# big_seven_v0_1.net
KiCad netlist of a schematic drawn in EAGLE
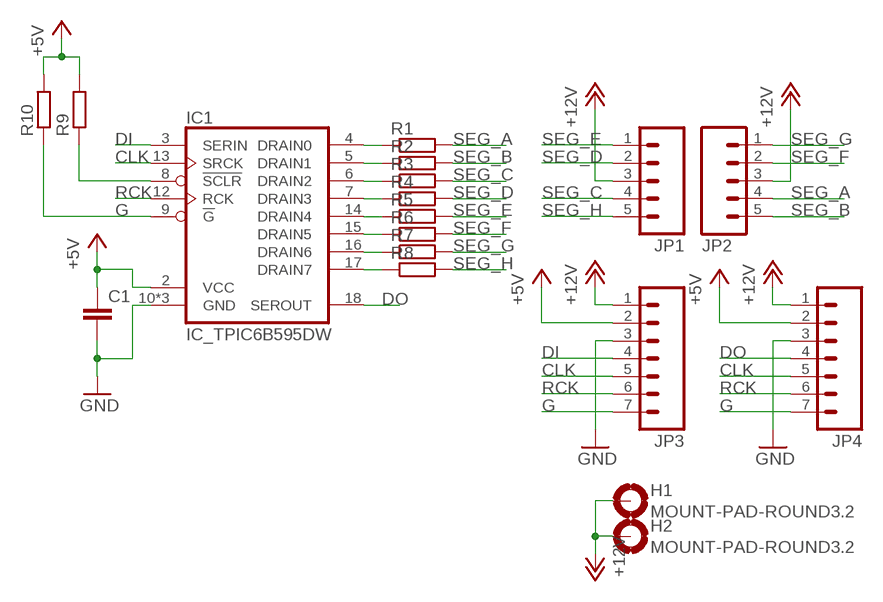
[diagram p0: schematic, sheet 1]

(export (version "E")
  (design (tool "Eeschema 10.0.6"))
  (components
    (comp (ref "C1")
      (value "C-EUC0805")
      (footprint "eagle-import:C0805")
      (libsource (lib "eagle-import") (part "C-EUC0805"))
    )
    (comp (ref "H1")
      (value "MOUNT-PAD-ROUND3.2")
      (footprint "eagle-import:3,2-PAD")
      (libsource (lib "eagle-import") (part "MOUNT-PAD-ROUND3.2"))
    )
    (comp (ref "H2")
      (value "MOUNT-PAD-ROUND3.2")
      (footprint "eagle-import:3,2-PAD")
      (libsource (lib "eagle-import") (part "MOUNT-PAD-ROUND3.2"))
    )
    (comp (ref "IC1")
      (value "IC_TPIC6B595DW")
      (footprint "eagle-import:SOIC-20")
      (libsource (lib "eagle-import") (part "IC_TPIC6B595DW"))
    )
    (comp (ref "JP1")
      (value "M05PTH")
      (footprint "eagle-import:1X05")
      (libsource (lib "eagle-import") (part "M05PTH"))
    )
    (comp (ref "JP2")
      (value "M05PTH")
      (footprint "eagle-import:1X05")
      (libsource (lib "eagle-import") (part "M05PTH"))
    )
    (comp (ref "JP3")
      (value "M07LONGPADS")
      (footprint "eagle-import:1X07_LONGPADS")
      (libsource (lib "eagle-import") (part "M07LONGPADS"))
    )
    (comp (ref "JP4")
      (value "M07LONGPADS")
      (footprint "eagle-import:1X07_LONGPADS")
      (libsource (lib "eagle-import") (part "M07LONGPADS"))
    )
    (comp (ref "R1")
      (value "R-EU_M0805")
      (footprint "eagle-import:M0805")
      (libsource (lib "eagle-import") (part "R-EU_M0805"))
    )
    (comp (ref "R2")
      (value "R-EU_M0805")
      (footprint "eagle-import:M0805")
      (libsource (lib "eagle-import") (part "R-EU_M0805"))
    )
    (comp (ref "R3")
      (value "R-EU_M0805")
      (footprint "eagle-import:M0805")
      (libsource (lib "eagle-import") (part "R-EU_M0805"))
    )
    (comp (ref "R4")
      (value "R-EU_M0805")
      (footprint "eagle-import:M0805")
      (libsource (lib "eagle-import") (part "R-EU_M0805"))
    )
    (comp (ref "R5")
      (value "R-EU_M0805")
      (footprint "eagle-import:M0805")
      (libsource (lib "eagle-import") (part "R-EU_M0805"))
    )
    (comp (ref "R6")
      (value "R-EU_M0805")
      (footprint "eagle-import:M0805")
      (libsource (lib "eagle-import") (part "R-EU_M0805"))
    )
    (comp (ref "R7")
      (value "R-EU_M0805")
      (footprint "eagle-import:M0805")
      (libsource (lib "eagle-import") (part "R-EU_M0805"))
    )
    (comp (ref "R8")
      (value "R-EU_M0805")
      (footprint "eagle-import:M0805")
      (libsource (lib "eagle-import") (part "R-EU_M0805"))
    )
    (comp (ref "R9")
      (value "R-EU_M0805")
      (footprint "eagle-import:M0805")
      (libsource (lib "eagle-import") (part "R-EU_M0805"))
    )
    (comp (ref "R10")
      (value "R-EU_M0805")
      (footprint "eagle-import:M0805")
      (libsource (lib "eagle-import") (part "R-EU_M0805"))
    )
  )
  (nets
    (net (code "1") (name "+5V") (class "Default")
      (node (ref "C1") (pin "1") (pinfunction "1_1") (pintype "passive"))
      (node (ref "IC1") (pin "2") (pinfunction "VCC_2") (pintype "power_in"))
      (node (ref "JP3") (pin "2") (pinfunction "2_2") (pintype "passive"))
      (node (ref "JP4") (pin "2") (pinfunction "2_2") (pintype "passive"))
      (node (ref "R10") (pin "2") (pinfunction "2_2") (pintype "passive"))
      (node (ref "R9") (pin "2") (pinfunction "2_2") (pintype "passive"))
    )
    (net (code "2") (name "+12V") (class "Default")
      (node (ref "H1") (pin "B3,2") (pinfunction "MOUNT_B3,2") (pintype "passive"))
      (node (ref "H2") (pin "B3,2") (pinfunction "MOUNT_B3,2") (pintype "passive"))
      (node (ref "JP1") (pin "3") (pinfunction "3_3") (pintype "passive"))
      (node (ref "JP2") (pin "3") (pinfunction "3_3") (pintype "passive"))
      (node (ref "JP3") (pin "1") (pinfunction "1_1") (pintype "passive"))
      (node (ref "JP4") (pin "1") (pinfunction "1_1") (pintype "passive"))
    )
    (net (code "3") (name "/CLK") (class "Default")
      (node (ref "IC1") (pin "13") (pinfunction "SRCK_13") (pintype "input"))
      (node (ref "JP3") (pin "5") (pinfunction "5_5") (pintype "passive"))
      (node (ref "JP4") (pin "5") (pinfunction "5_5") (pintype "passive"))
    )
    (net (code "4") (name "/DI") (class "Default")
      (node (ref "IC1") (pin "3") (pinfunction "SERIN_3") (pintype "input"))
      (node (ref "JP3") (pin "4") (pinfunction "4_4") (pintype "passive"))
    )
    (net (code "5") (name "/DO") (class "Default")
      (node (ref "IC1") (pin "18") (pinfunction "SEROUT_18") (pintype "output"))
      (node (ref "JP4") (pin "4") (pinfunction "4_4") (pintype "passive"))
    )
    (net (code "6") (name "/G") (class "Default")
      (node (ref "IC1") (pin "9") (pinfunction "~{G}_9") (pintype "input"))
      (node (ref "JP3") (pin "7") (pinfunction "7_7") (pintype "passive"))
      (node (ref "JP4") (pin "7") (pinfunction "7_7") (pintype "passive"))
      (node (ref "R10") (pin "1") (pinfunction "1_1") (pintype "passive"))
    )
    (net (code "7") (name "/RCK") (class "Default")
      (node (ref "IC1") (pin "12") (pinfunction "RCK_12") (pintype "input"))
      (node (ref "JP3") (pin "6") (pinfunction "6_6") (pintype "passive"))
      (node (ref "JP4") (pin "6") (pinfunction "6_6") (pintype "passive"))
    )
    (net (code "8") (name "/SEG_A") (class "Default")
      (node (ref "JP2") (pin "4") (pinfunction "4_4") (pintype "passive"))
      (node (ref "R1") (pin "2") (pinfunction "2_2") (pintype "passive"))
    )
    (net (code "9") (name "/SEG_B") (class "Default")
      (node (ref "JP2") (pin "5") (pinfunction "5_5") (pintype "passive"))
      (node (ref "R2") (pin "2") (pinfunction "2_2") (pintype "passive"))
    )
    (net (code "10") (name "/SEG_C") (class "Default")
      (node (ref "JP1") (pin "4") (pinfunction "4_4") (pintype "passive"))
      (node (ref "R3") (pin "2") (pinfunction "2_2") (pintype "passive"))
    )
    (net (code "11") (name "/SEG_D") (class "Default")
      (node (ref "JP1") (pin "2") (pinfunction "2_2") (pintype "passive"))
      (node (ref "R4") (pin "2") (pinfunction "2_2") (pintype "passive"))
    )
    (net (code "12") (name "/SEG_E") (class "Default")
      (node (ref "JP1") (pin "1") (pinfunction "1_1") (pintype "passive"))
      (node (ref "R5") (pin "2") (pinfunction "2_2") (pintype "passive"))
    )
    (net (code "13") (name "/SEG_F") (class "Default")
      (node (ref "JP2") (pin "2") (pinfunction "2_2") (pintype "passive"))
      (node (ref "R6") (pin "2") (pinfunction "2_2") (pintype "passive"))
    )
    (net (code "14") (name "/SEG_G") (class "Default")
      (node (ref "JP2") (pin "1") (pinfunction "1_1") (pintype "passive"))
      (node (ref "R7") (pin "2") (pinfunction "2_2") (pintype "passive"))
    )
    (net (code "15") (name "/SEG_H") (class "Default")
      (node (ref "JP1") (pin "5") (pinfunction "5_5") (pintype "passive"))
      (node (ref "R8") (pin "2") (pinfunction "2_2") (pintype "passive"))
    )
    (net (code "16") (name "GND") (class "Default")
      (node (ref "C1") (pin "2") (pinfunction "2_2") (pintype "passive"))
      (node (ref "IC1") (pin "10") (pinfunction "GND_10") (pintype "power_in"))
      (node (ref "IC1") (pin "11") (pinfunction "GND_11") (pintype "power_in"))
      (node (ref "IC1") (pin "19") (pinfunction "GND_19") (pintype "power_in"))
      (node (ref "JP3") (pin "3") (pinfunction "3_3") (pintype "passive"))
      (node (ref "JP4") (pin "3") (pinfunction "3_3") (pintype "passive"))
    )
    (net (code "17") (name "Net-(IC1-DRAIN0)") (class "Default")
      (node (ref "IC1") (pin "4") (pinfunction "DRAIN0_4") (pintype "output"))
      (node (ref "R1") (pin "1") (pinfunction "1_1") (pintype "passive"))
    )
    (net (code "18") (name "Net-(IC1-DRAIN1)") (class "Default")
      (node (ref "IC1") (pin "5") (pinfunction "DRAIN1_5") (pintype "output"))
      (node (ref "R2") (pin "1") (pinfunction "1_1") (pintype "passive"))
    )
    (net (code "19") (name "Net-(IC1-DRAIN2)") (class "Default")
      (node (ref "IC1") (pin "6") (pinfunction "DRAIN2_6") (pintype "output"))
      (node (ref "R3") (pin "1") (pinfunction "1_1") (pintype "passive"))
    )
    (net (code "20") (name "Net-(IC1-DRAIN3)") (class "Default")
      (node (ref "IC1") (pin "7") (pinfunction "DRAIN3_7") (pintype "output"))
      (node (ref "R4") (pin "1") (pinfunction "1_1") (pintype "passive"))
    )
    (net (code "21") (name "Net-(IC1-DRAIN4)") (class "Default")
      (node (ref "IC1") (pin "14") (pinfunction "DRAIN4_14") (pintype "output"))
      (node (ref "R5") (pin "1") (pinfunction "1_1") (pintype "passive"))
    )
    (net (code "22") (name "Net-(IC1-DRAIN5)") (class "Default")
      (node (ref "IC1") (pin "15") (pinfunction "DRAIN5_15") (pintype "output"))
      (node (ref "R6") (pin "1") (pinfunction "1_1") (pintype "passive"))
    )
    (net (code "23") (name "Net-(IC1-DRAIN6)") (class "Default")
      (node (ref "IC1") (pin "16") (pinfunction "DRAIN6_16") (pintype "output"))
      (node (ref "R7") (pin "1") (pinfunction "1_1") (pintype "passive"))
    )
    (net (code "24") (name "Net-(IC1-DRAIN7)") (class "Default")
      (node (ref "IC1") (pin "17") (pinfunction "DRAIN7_17") (pintype "output"))
      (node (ref "R8") (pin "1") (pinfunction "1_1") (pintype "passive"))
    )
    (net (code "25") (name "Net-(IC1-~{SCLR})") (class "Default")
      (node (ref "IC1") (pin "8") (pinfunction "~{SCLR}_8") (pintype "input"))
      (node (ref "R9") (pin "1") (pinfunction "1_1") (pintype "passive"))
    )
  )
)
